# Main.net
KiCad netlist of a schematic drawn in Altium Designer
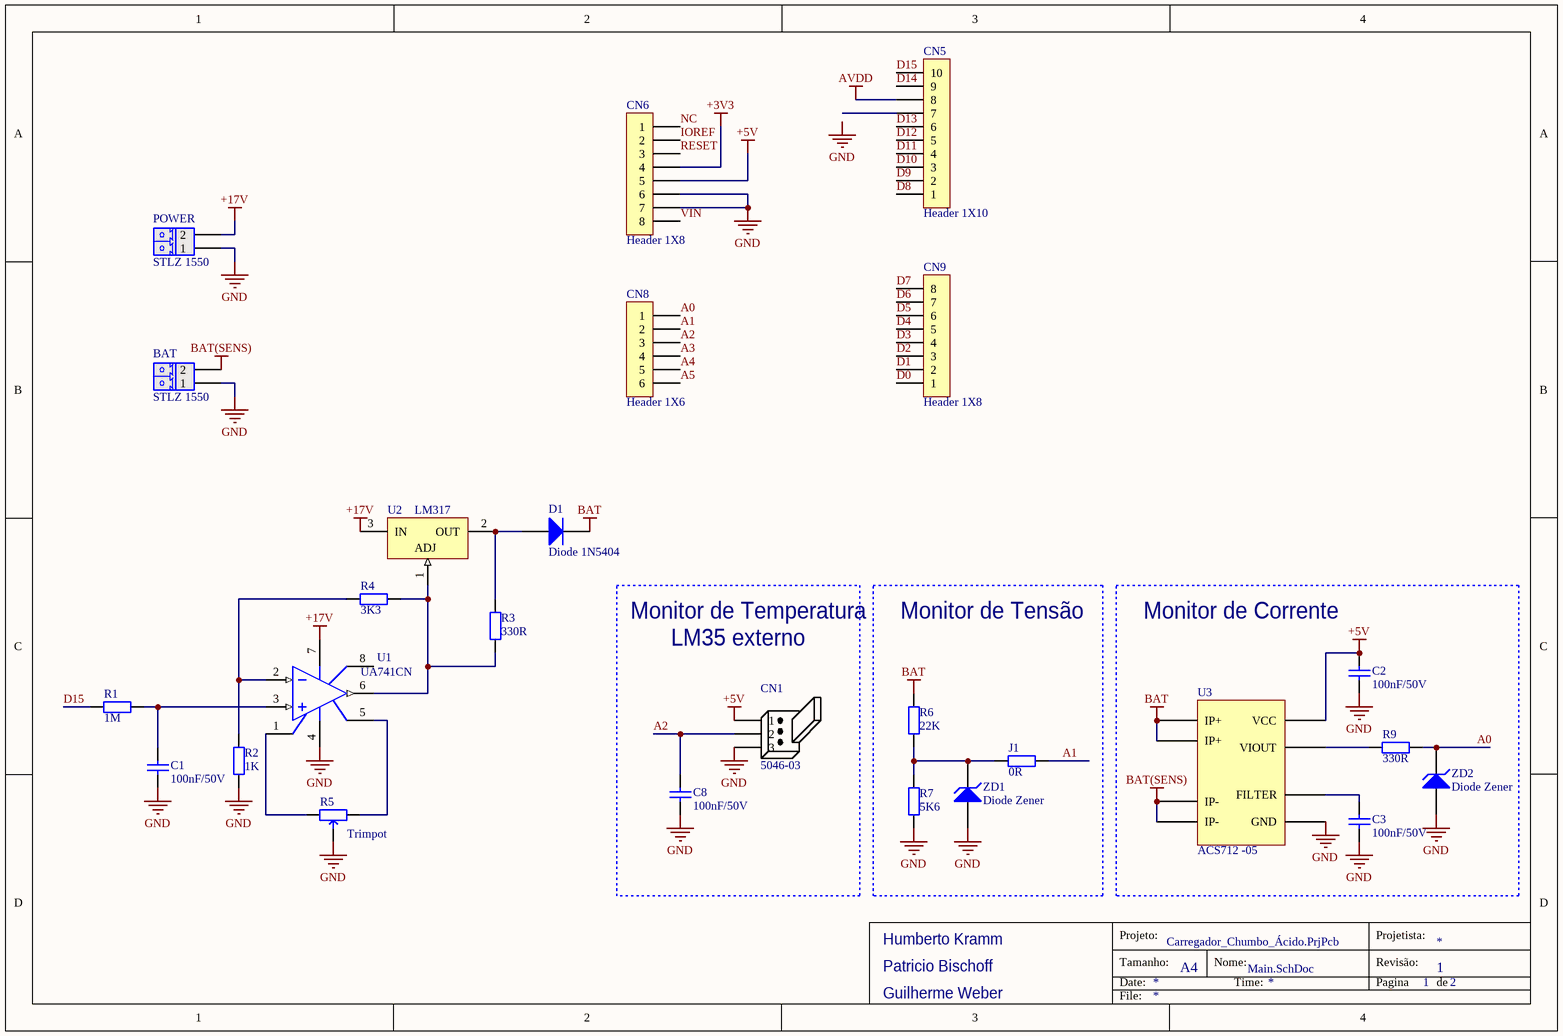
[diagram p0: Main.SchDoc]

(export (version "E")
  (design (tool "Eeschema 10.0.6"))
  (components
    (comp (ref "BAT")
      (value "STLZ 1550")
      (footprint "STLZ 1550 H 02 PIN")
      (description "CONECTOR STLZ 1550 2pin Horizontal")
      (libsource (lib "almox Gaia") (part "CONECTOR STLZ 1550/02G H"))
    )
    (comp (ref "C1")
      (value "100nF/50V")
      (footprint "CAP 0805")
      (description "Capacitor Cerâmico")
      (fields (field (name "Comment") "Cap.Cer. 100nF/50V SMD") (field (name "PUBLISHER") "Altium Limited"))
      (libsource (lib "almox Gaia") (part "Cap.Cer. 100nF/50V SMD"))
    )
    (comp (ref "C2")
      (value "100nF/50V")
      (footprint "CAP 0805")
      (description "Capacitor Cerâmico")
      (fields (field (name "Comment") "Cap.Cer. 100nF/50V SMD") (field (name "PUBLISHER") "Altium Limited"))
      (libsource (lib "almox Gaia") (part "Cap.Cer. 100nF/50V SMD"))
    )
    (comp (ref "C3")
      (value "100nF/50V")
      (footprint "CAP 0805")
      (description "Capacitor Cerâmico")
      (fields (field (name "Comment") "Cap.Cer. 100nF/50V SMD") (field (name "PUBLISHER") "Altium Limited"))
      (libsource (lib "almox Gaia") (part "Cap.Cer. 100nF/50V SMD"))
    )
    (comp (ref "C8")
      (value "100nF/50V")
      (footprint "CAP 0805")
      (description "Capacitor Cerâmico")
      (fields (field (name "Comment") "Cap.Cer. 100nF/50V SMD") (field (name "PUBLISHER") "Altium Limited"))
      (libsource (lib "almox Gaia") (part "Cap.Cer. 100nF/50V SMD"))
    )
    (comp (ref "CN1")
      (value "5046-03")
      (footprint "5046-03")
      (description "CONECTOR MOLEX KK 5045 90° 2,54mm  3 VIAS")
      (fields (field (name "PUBLISHER") "Altium Limited"))
      (libsource (lib "almox Gaia") (part "CONECTOR 5046-03"))
    )
    (comp (ref "CN5")
      (value "Header 1X10")
      (footprint "HEADER 1x10")
      (description "Header, 10-Pin, single row, right angle")
      (fields (field (name "PUBLISHER") "Altium Limited"))
      (libsource (lib "almox Gaia") (part "Header 1X10"))
    )
    (comp (ref "CN6")
      (value "Header 1X8")
      (footprint "HEADER 1x8")
      (description "Header, 8-Pin, single row")
      (fields (field (name "PUBLISHER") "Altium Limited"))
      (libsource (lib "") (part "Header 1X8_1"))
    )
    (comp (ref "CN8")
      (value "Header 1X6")
      (footprint "HEADER 1x6")
      (description "Header, 6-Pin, single row")
      (fields (field (name "PUBLISHER") "Altium Limited"))
      (libsource (lib "almox Gaia") (part "Header 1X6"))
    )
    (comp (ref "CN9")
      (value "Header 1X8")
      (footprint "HEADER 1x8")
      (description "Header, 8-Pin, single row")
      (fields (field (name "PUBLISHER") "Altium Limited"))
      (libsource (lib "almox Gaia") (part "Header 1X8"))
    )
    (comp (ref "D1")
      (value "Diode 1N5404")
      (footprint "DO-201AD")
      (description "3 Amp General Purpose Rectifier")
      (fields (field (name "PUBLISHER") "Altium Limited"))
      (libsource (lib "almox Gaia") (part "Diode 1N5404"))
    )
    (comp (ref "J1")
      (value "0R")
      (footprint "RES 0805")
      (description "Resistor")
      (fields (field (name "Comment") "Res 0R SMD") (field (name "PUBLISHER") "Altium Limited"))
      (libsource (lib "almox Gaia") (part "Res 0R SMD"))
    )
    (comp (ref "POWER")
      (value "STLZ 1550")
      (footprint "STLZ 1550 H 02 PIN")
      (description "CONECTOR STLZ 1550 2pin Horizontal")
      (libsource (lib "almox Gaia") (part "CONECTOR STLZ 1550/02G H"))
    )
    (comp (ref "R1")
      (value "1M")
      (footprint "RES 0805")
      (description "Resistor")
      (fields (field (name "Comment") "Res 2M SMD") (field (name "PUBLISHER") "Altium Limited"))
      (libsource (lib "almox Gaia") (part "Res 2M SMD"))
    )
    (comp (ref "R2")
      (value "1K")
      (footprint "RES 0805")
      (description "Resistor")
      (fields (field (name "Comment") "Res 1K SMD") (field (name "PUBLISHER") "Altium Limited"))
      (libsource (lib "almox Gaia") (part "Res 1K SMD"))
    )
    (comp (ref "R3")
      (value "330R")
      (footprint "RES 0805")
      (description "Resistor")
      (fields (field (name "Comment") "Res 330R SMD") (field (name "PUBLISHER") "Altium Limited"))
      (libsource (lib "") (part "Res 330R SMD_1"))
    )
    (comp (ref "R4")
      (value "3K3")
      (footprint "RES 0805")
      (description "Resistor")
      (fields (field (name "Comment") "Res 3K3 SMD") (field (name "PUBLISHER") "Altium Limited"))
      (libsource (lib "almox Gaia") (part "Res 3K3 SMD"))
    )
    (comp (ref "R5")
      (value "Trimpot")
      (footprint "3006P")
      (description "Variable Resistor")
      (fields (field (name "PUBLISHER") "Altium Limited"))
      (libsource (lib "almox Gaia") (part "Trimpot"))
    )
    (comp (ref "R6")
      (value "22K")
      (footprint "RES 0805")
      (description "Resistor")
      (fields (field (name "Comment") "Res 22K SMD") (field (name "PUBLISHER") "Altium Limited"))
      (libsource (lib "almox Gaia") (part "Res 22K SMD"))
    )
    (comp (ref "R7")
      (value "5K6")
      (footprint "RES 0805")
      (description "Resistor")
      (fields (field (name "Comment") "Res 5K6 SMD") (field (name "PUBLISHER") "Altium Limited"))
      (libsource (lib "almox Gaia") (part "Res 5K6 SMD"))
    )
    (comp (ref "R9")
      (value "330R")
      (footprint "RES 0805")
      (description "Resistor")
      (fields (field (name "Comment") "Res 330R SMD") (field (name "PUBLISHER") "Altium Limited"))
      (libsource (lib "almox Gaia") (part "Res 330R SMD"))
    )
    (comp (ref "U1")
      (value "UA741CN")
      (footprint "PDIP300-P8")
      (description "General-Purpose Single Operational Amplifier")
      (fields (field (name "PUBLISHER") "Altium Limited"))
      (libsource (lib "ST Operational Amplifier") (part "UA741CN"))
    )
    (comp (ref "U2")
      (value "LM317")
      (footprint "TO-220A 90°")
      (description "Positive Voltage Regulator")
      (fields (field (name "PUBLISHER") "Altium Limited"))
      (libsource (lib "almox Gaia") (part "LM317"))
    )
    (comp (ref "U3")
      (value "ACS712 -05")
      (footprint "SOIC-08")
      (description "Sensor de Efeito Hall")
      (fields (field (name "PUBLISHER") "Altium Limited"))
      (libsource (lib "almox Gaia") (part "ACS712 -05"))
    )
    (comp (ref "ZD1")
      (value "Diode Zener")
      (footprint "MINI MELF")
      (description "Zener Diode")
      (fields (field (name "PUBLISHER") "Altium Limited"))
      (libsource (lib "almox Gaia") (part "Diode Zener SMD 4,7V"))
    )
    (comp (ref "ZD2")
      (value "Diode Zener")
      (footprint "MINI MELF")
      (description "Zener Diode")
      (fields (field (name "PUBLISHER") "Altium Limited"))
      (libsource (lib "almox Gaia") (part "Diode Zener SMD 4,7V"))
    )
  )
  (nets
    (net (code "1") (name "+3V3") (class "Default")
      (node (ref "CN6") (pin "4") (pinfunction "4_4") (pintype "passive"))
    )
    (net (code "2") (name "+5V") (class "Default")
      (node (ref "C2") (pin "1") (pinfunction "1_1") (pintype "passive"))
      (node (ref "CN1") (pin "1") (pinfunction "1_1") (pintype "passive"))
      (node (ref "CN6") (pin "5") (pinfunction "5_5") (pintype "passive"))
      (node (ref "U3") (pin "8") (pinfunction "VCC_8") (pintype "passive"))
    )
    (net (code "3") (name "+17V") (class "Default")
      (node (ref "POWER") (pin "2") (pinfunction "2_2") (pintype "passive"))
      (node (ref "U1") (pin "7") (pinfunction "V+_7") (pintype "power_in"))
      (node (ref "U2") (pin "3") (pinfunction "IN_3") (pintype "power_in"))
    )
    (net (code "4") (name "/A0") (class "Default")
      (node (ref "CN8") (pin "1") (pinfunction "1_1") (pintype "passive"))
      (node (ref "R9") (pin "2") (pinfunction "2_2") (pintype "passive"))
      (node (ref "ZD2") (pin "2") (pinfunction "K_2") (pintype "passive"))
    )
    (net (code "5") (name "/A1") (class "Default")
      (node (ref "CN8") (pin "2") (pinfunction "2_2") (pintype "passive"))
      (node (ref "J1") (pin "2") (pinfunction "2_2") (pintype "passive"))
    )
    (net (code "6") (name "/A2") (class "Default")
      (node (ref "C8") (pin "2") (pinfunction "2_2") (pintype "passive"))
      (node (ref "CN1") (pin "2") (pinfunction "2_2") (pintype "passive"))
      (node (ref "CN8") (pin "3") (pinfunction "3_3") (pintype "passive"))
    )
    (net (code "7") (name "/A3") (class "Default")
      (node (ref "CN8") (pin "4") (pinfunction "4_4") (pintype "passive"))
    )
    (net (code "8") (name "/A4") (class "Default")
      (node (ref "CN8") (pin "5") (pinfunction "5_5") (pintype "passive"))
    )
    (net (code "9") (name "/A5") (class "Default")
      (node (ref "CN8") (pin "6") (pinfunction "6_6") (pintype "passive"))
    )
    (net (code "10") (name "/D0") (class "Default")
      (node (ref "CN9") (pin "1") (pinfunction "1_1") (pintype "passive"))
    )
    (net (code "11") (name "/D1") (class "Default")
      (node (ref "CN9") (pin "2") (pinfunction "2_2") (pintype "passive"))
    )
    (net (code "12") (name "/D2") (class "Default")
      (node (ref "CN9") (pin "3") (pinfunction "3_3") (pintype "passive"))
    )
    (net (code "13") (name "/D3") (class "Default")
      (node (ref "CN9") (pin "4") (pinfunction "4_4") (pintype "passive"))
    )
    (net (code "14") (name "/D4") (class "Default")
      (node (ref "CN9") (pin "5") (pinfunction "5_5") (pintype "passive"))
    )
    (net (code "15") (name "/D5") (class "Default")
      (node (ref "CN9") (pin "6") (pinfunction "6_6") (pintype "passive"))
    )
    (net (code "16") (name "/D6") (class "Default")
      (node (ref "CN9") (pin "7") (pinfunction "7_7") (pintype "passive"))
    )
    (net (code "17") (name "/D7") (class "Default")
      (node (ref "CN9") (pin "8") (pinfunction "8_8") (pintype "passive"))
    )
    (net (code "18") (name "/D8") (class "Default")
      (node (ref "CN5") (pin "1") (pinfunction "1_1") (pintype "passive"))
    )
    (net (code "19") (name "/D9") (class "Default")
      (node (ref "CN5") (pin "2") (pinfunction "2_2") (pintype "passive"))
    )
    (net (code "20") (name "/D10") (class "Default")
      (node (ref "CN5") (pin "3") (pinfunction "3_3") (pintype "passive"))
    )
    (net (code "21") (name "/D11") (class "Default")
      (node (ref "CN5") (pin "4") (pinfunction "4_4") (pintype "passive"))
    )
    (net (code "22") (name "/D12") (class "Default")
      (node (ref "CN5") (pin "5") (pinfunction "5_5") (pintype "passive"))
    )
    (net (code "23") (name "/D13") (class "Default")
      (node (ref "CN5") (pin "6") (pinfunction "6_6") (pintype "passive"))
    )
    (net (code "24") (name "/D14") (class "Default")
      (node (ref "CN5") (pin "9") (pinfunction "9_9") (pintype "passive"))
    )
    (net (code "25") (name "/D15") (class "Default")
      (node (ref "CN5") (pin "10") (pinfunction "10_10") (pintype "passive"))
      (node (ref "R1") (pin "1") (pinfunction "1_1") (pintype "passive"))
    )
    (net (code "26") (name "/IOREF") (class "Default")
      (node (ref "CN6") (pin "2") (pinfunction "2_2") (pintype "passive"))
    )
    (net (code "27") (name "/NC") (class "Default")
      (node (ref "CN6") (pin "1") (pinfunction "1_1") (pintype "passive"))
    )
    (net (code "28") (name "/RESET") (class "Default")
      (node (ref "CN6") (pin "3") (pinfunction "3_3") (pintype "passive"))
    )
    (net (code "29") (name "/VIN") (class "Default")
      (node (ref "CN6") (pin "8") (pinfunction "8_8") (pintype "passive"))
    )
    (net (code "30") (name "AVDD") (class "Default")
      (node (ref "CN5") (pin "8") (pinfunction "8_8") (pintype "passive"))
    )
    (net (code "31") (name "BAT") (class "Default")
      (node (ref "D1") (pin "2") (pinfunction "K_2") (pintype "passive"))
      (node (ref "R6") (pin "2") (pinfunction "2_2") (pintype "passive"))
      (node (ref "U3") (pin "1") (pinfunction "IP+_1") (pintype "passive"))
      (node (ref "U3") (pin "2") (pinfunction "IP+_2") (pintype "passive"))
    )
    (net (code "32") (name "BAT(SENS)") (class "Default")
      (node (ref "BAT") (pin "2") (pinfunction "2_2") (pintype "passive"))
      (node (ref "U3") (pin "3") (pinfunction "IP-_3") (pintype "passive"))
      (node (ref "U3") (pin "4") (pinfunction "IP-_4") (pintype "passive"))
    )
    (net (code "33") (name "GND") (class "Default")
      (node (ref "BAT") (pin "1") (pinfunction "1_1") (pintype "passive"))
      (node (ref "C1") (pin "1") (pinfunction "1_1") (pintype "passive"))
      (node (ref "C2") (pin "2") (pinfunction "2_2") (pintype "passive"))
      (node (ref "C3") (pin "2") (pinfunction "2_2") (pintype "passive"))
      (node (ref "C8") (pin "1") (pinfunction "1_1") (pintype "passive"))
      (node (ref "CN1") (pin "3") (pinfunction "3_3") (pintype "passive"))
      (node (ref "CN6") (pin "6") (pinfunction "6_6") (pintype "passive"))
      (node (ref "CN6") (pin "7") (pinfunction "7_7") (pintype "passive"))
      (node (ref "POWER") (pin "1") (pinfunction "1_1") (pintype "passive"))
      (node (ref "R2") (pin "1") (pinfunction "1_1") (pintype "passive"))
      (node (ref "R5") (pin "2") (pinfunction "2_2") (pintype "passive"))
      (node (ref "R7") (pin "1") (pinfunction "1_1") (pintype "passive"))
      (node (ref "U1") (pin "4") (pinfunction "V-_4") (pintype "power_in"))
      (node (ref "U3") (pin "5") (pinfunction "GND_5") (pintype "passive"))
      (node (ref "ZD1") (pin "1") (pinfunction "A_1") (pintype "passive"))
      (node (ref "ZD2") (pin "1") (pinfunction "A_1") (pintype "passive"))
    )
    (net (code "34") (name "Net-(D1-A)") (class "Default")
      (node (ref "D1") (pin "1") (pinfunction "A_1") (pintype "passive"))
      (node (ref "R3") (pin "2") (pinfunction "2_2") (pintype "passive"))
      (node (ref "U2") (pin "2") (pinfunction "OUT_2") (pintype "power_in"))
    )
    (net (code "35") (name "Net-(R5-Pad1)") (class "Default")
      (node (ref "R5") (pin "1") (pinfunction "1_1") (pintype "passive"))
      (node (ref "U1") (pin "5") (pinfunction "OS_NULL_5") (pintype "passive"))
    )
    (net (code "36") (name "Net-(R5-Pad3)") (class "Default")
      (node (ref "R5") (pin "3") (pinfunction "3_3") (pintype "passive"))
      (node (ref "U1") (pin "1") (pinfunction "OS_NULL_1") (pintype "passive"))
    )
    (net (code "37") (name "Net-(U1-IN+)") (class "Default")
      (node (ref "C1") (pin "2") (pinfunction "2_2") (pintype "passive"))
      (node (ref "R1") (pin "2") (pinfunction "2_2") (pintype "passive"))
      (node (ref "U1") (pin "3") (pinfunction "IN+_3") (pintype "input"))
    )
    (net (code "38") (name "Net-(U1-IN-)") (class "Default")
      (node (ref "R2") (pin "2") (pinfunction "2_2") (pintype "passive"))
      (node (ref "R4") (pin "1") (pinfunction "1_1") (pintype "passive"))
      (node (ref "U1") (pin "2") (pinfunction "IN-_2") (pintype "input"))
    )
    (net (code "39") (name "Net-(U1-OUT)") (class "Default")
      (node (ref "R3") (pin "1") (pinfunction "1_1") (pintype "passive"))
      (node (ref "R4") (pin "2") (pinfunction "2_2") (pintype "passive"))
      (node (ref "U1") (pin "6") (pinfunction "OUT_6") (pintype "output"))
      (node (ref "U2") (pin "1") (pinfunction "ADJ_1") (pintype "input"))
    )
    (net (code "40") (name "Net-(U3-FILTER)") (class "Default")
      (node (ref "C3") (pin "1") (pinfunction "1_1") (pintype "passive"))
      (node (ref "U3") (pin "6") (pinfunction "FILTER_6") (pintype "passive"))
    )
    (net (code "41") (name "Net-(U3-VIOUT)") (class "Default")
      (node (ref "R9") (pin "1") (pinfunction "1_1") (pintype "passive"))
      (node (ref "U3") (pin "7") (pinfunction "VIOUT_7") (pintype "passive"))
    )
    (net (code "42") (name "Net-(ZD1-K)") (class "Default")
      (node (ref "J1") (pin "1") (pinfunction "1_1") (pintype "passive"))
      (node (ref "R6") (pin "1") (pinfunction "1_1") (pintype "passive"))
      (node (ref "R7") (pin "2") (pinfunction "2_2") (pintype "passive"))
      (node (ref "ZD1") (pin "2") (pinfunction "K_2") (pintype "passive"))
    )
    (net (code "43") (name "unconnected-(CN5-Pad7)") (class "Default")
      (node (ref "CN5") (pin "7") (pinfunction "7_7") (pintype "passive"))
    )
    (net (code "44") (name "unconnected-(U1-NC-Pad8)") (class "Default")
      (node (ref "U1") (pin "8") (pinfunction "NC_8") (pintype "passive"))
    )
  )
)
